# Margay.net
KiCad netlist of a schematic drawn in EAGLE
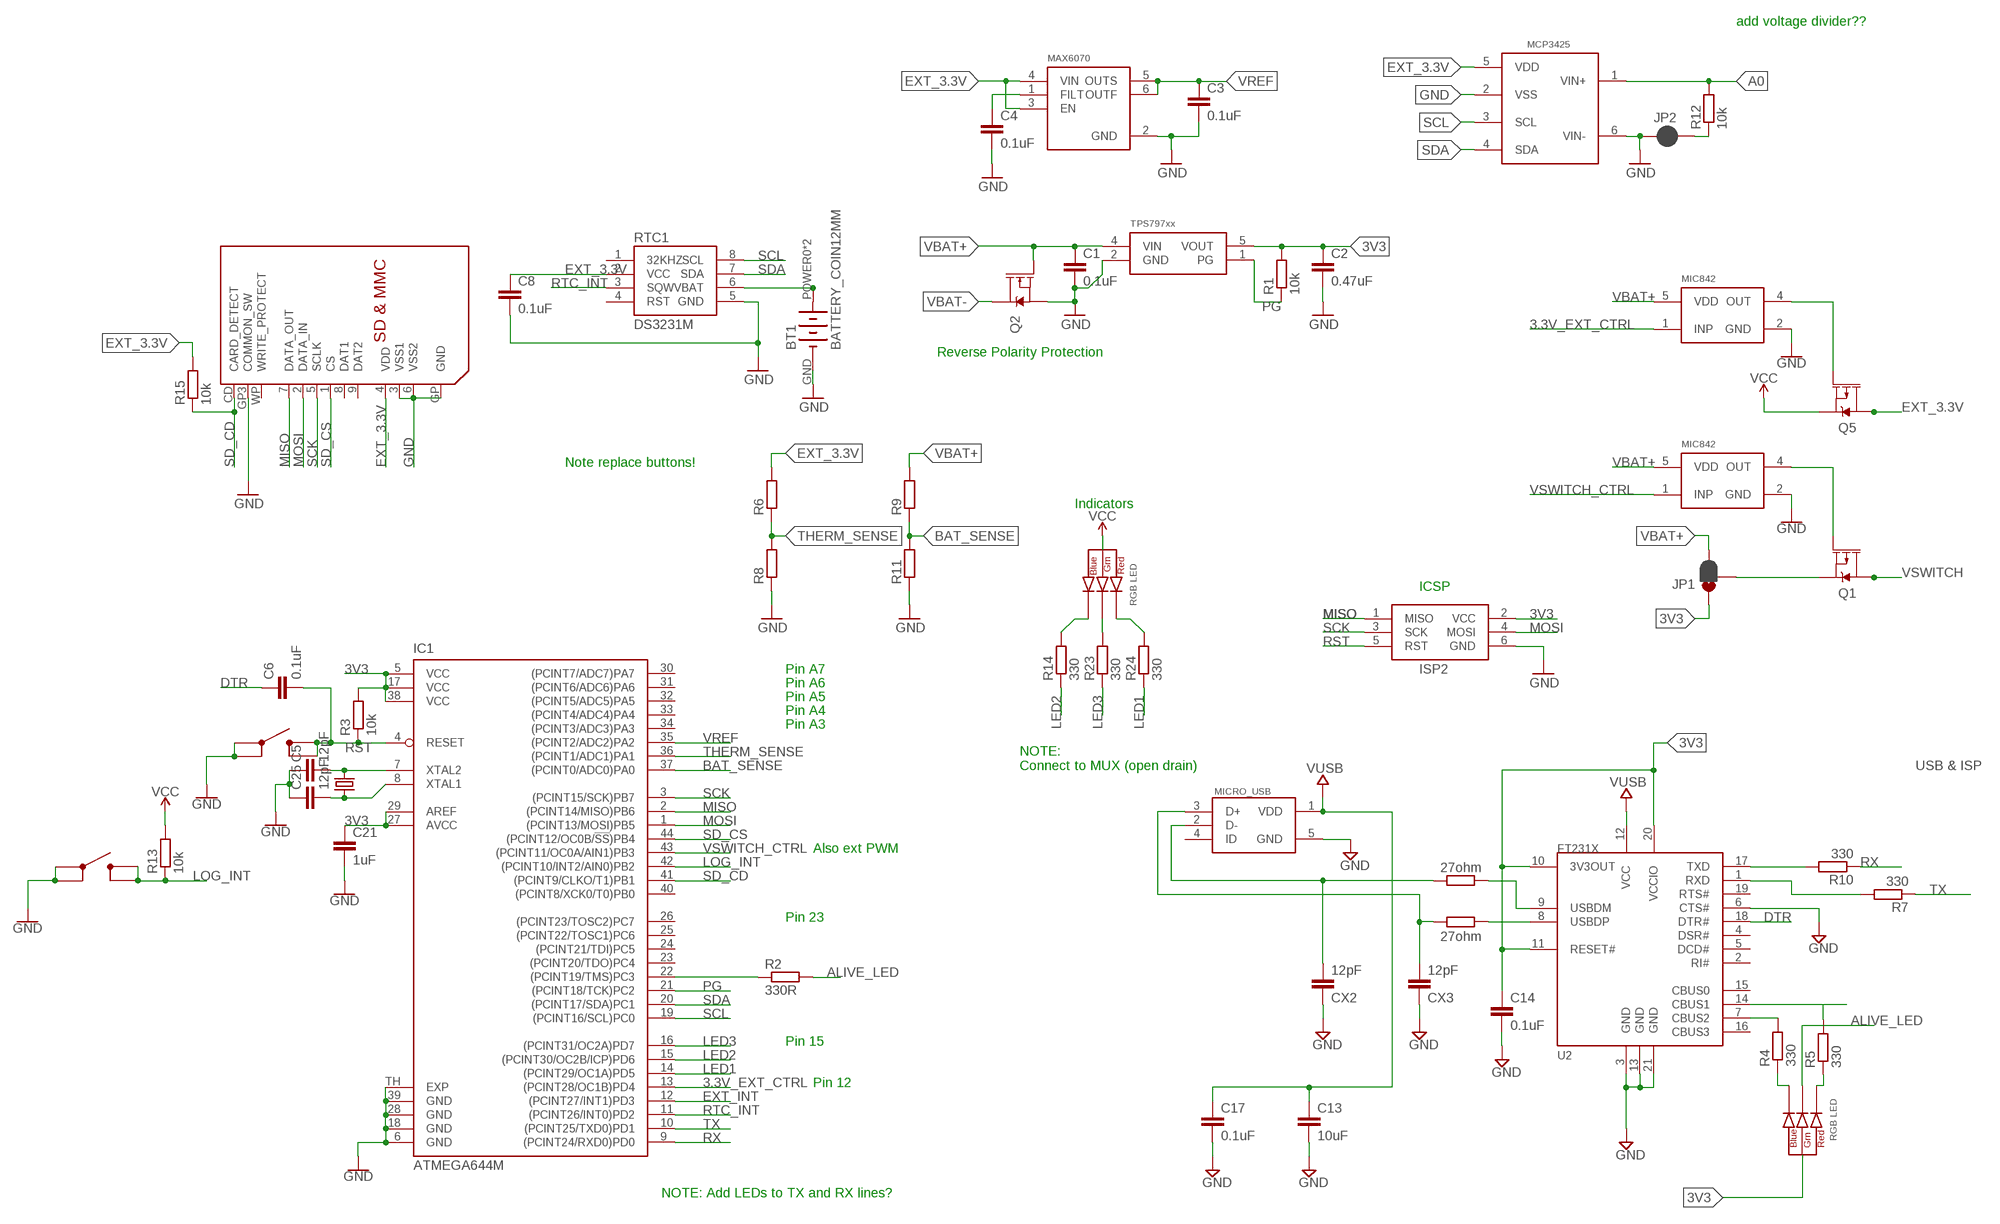
[diagram p0: schematic, sheet 1]
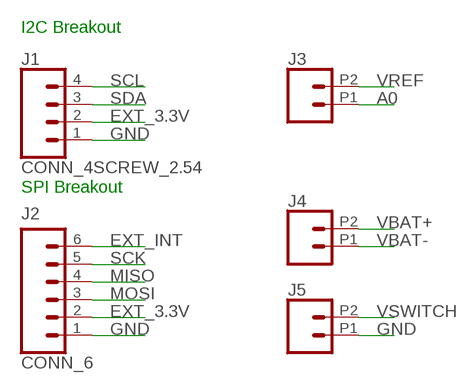
[diagram p1: schematic, sheet 2]

(export (version "E")
  (design (tool "Eeschema 10.0.6"))
  (components
    (comp (ref "J1")
      (value "CONN_4SCREW_2.54")
      (footprint "eagle-import:1X04")
      (libsource (lib "eagle-import") (part "CONN_4SCREW_2.54"))
    )
    (comp (ref "J2")
      (value "CONN_6")
      (footprint "eagle-import:1X06_SCREW")
      (libsource (lib "eagle-import") (part "CONN_6"))
    )
    (comp (ref "J3")
      (value "CONN_022.54MM_SCREWTERM")
      (footprint "eagle-import:1X02_2.54_SCREWTERM")
      (libsource (lib "eagle-import") (part "CONN_022.54MM_SCREWTERM"))
    )
    (comp (ref "J4")
      (value "CONN_022.54MM_SCREWTERM")
      (footprint "eagle-import:1X02_2.54_SCREWTERM")
      (libsource (lib "eagle-import") (part "CONN_022.54MM_SCREWTERM"))
    )
    (comp (ref "J5")
      (value "CONN_022.54MM_SCREWTERM")
      (footprint "eagle-import:1X02_2.54_SCREWTERM")
      (libsource (lib "eagle-import") (part "CONN_022.54MM_SCREWTERM"))
    )
    (comp (ref "BT1")
      (value "BATTERY_COIN12MM")
      (footprint "eagle-import:AWICKERT_LINX_BAT-HLD-012-SMT")
      (fields (field (name "MF") "Linx") (field (name "MPN") "BAT-HLD-012-SMT"))
      (libsource (lib "eagle-import") (part "BATTERY_COIN12MM"))
    )
    (comp (ref "C1")
      (value "0.1uF")
      (footprint "eagle-import:C0603")
      (libsource (lib "eagle-import") (part "bschulz_passives_C-EUC0603"))
    )
    (comp (ref "C2")
      (value "0.47uF")
      (footprint "eagle-import:C0603")
      (libsource (lib "eagle-import") (part "bschulz_passives_C-EUC0603"))
    )
    (comp (ref "C3")
      (value "0.1uF")
      (footprint "eagle-import:C0603")
      (libsource (lib "eagle-import") (part "bschulz_passives_C-EUC0603"))
    )
    (comp (ref "C4")
      (value "0.1uF")
      (footprint "eagle-import:C0603")
      (libsource (lib "eagle-import") (part "bschulz_passives_C-EUC0603"))
    )
    (comp (ref "C5")
      (value "12pF")
      (footprint "eagle-import:C0603")
      (fields
        (field (name "MF") "Samsung")
        (field (name "MPN") "CL10C120JB8NNNC")
        (field (name "DIGIKEY") "1276-1254-1-ND")
        (field (name "MF_1") "Samsung")
        (field (name "MPN_1") "CL10C120JB8NNNC")
      )
      (libsource (lib "eagle-import") (part "C-EUC060312PF"))
    )
    (comp (ref "C6")
      (value "0.1uF")
      (footprint "eagle-import:C0603")
      (fields (field (name "MF") "Samsung") (field (name "MPN") "CL10B104KO8NNNC"))
      (libsource (lib "eagle-import") (part "C-EUC06030.1UF"))
    )
    (comp (ref "C8")
      (value "0.1uF")
      (footprint "eagle-import:C0603")
      (libsource (lib "eagle-import") (part "C-EUC0603"))
    )
    (comp (ref "C13")
      (value "10uF")
      (footprint "eagle-import:C0805")
      (fields (field (name "MF") "Samsung") (field (name "MPN") "CL21A106KQCLRNC"))
      (libsource (lib "eagle-import") (part "C-EUC080510UF"))
    )
    (comp (ref "C14")
      (value "0.1uF")
      (footprint "eagle-import:C0603")
      (fields (field (name "MF") "Samsung") (field (name "MPN") "CL10B104KO8NNNC"))
      (libsource (lib "eagle-import") (part "C-EUC06030.1UF"))
    )
    (comp (ref "C17")
      (value "0.1uF")
      (footprint "eagle-import:C0603")
      (fields (field (name "MF") "Samsung") (field (name "MPN") "CL10B104KO8NNNC"))
      (libsource (lib "eagle-import") (part "C-EUC06030.1UF"))
    )
    (comp (ref "C21")
      (value "1uF")
      (footprint "eagle-import:C0603")
      (fields
        (field (name "MF") "Samsung")
        (field (name "MPN") "1276-6524-1-ND")
        (field (name "DIGIKEY") "1276-6524-1-ND")
        (field (name "MF_1") "Samsung")
        (field (name "MPN_1") "CL10B105MO8NNWC")
      )
      (libsource (lib "eagle-import") (part "C-EUC06031UF"))
    )
    (comp (ref "C25")
      (value "12pF")
      (footprint "eagle-import:C0603")
      (fields
        (field (name "MF") "Samsung")
        (field (name "MPN") "CL10C120JB8NNNC")
        (field (name "DIGIKEY") "1276-1254-1-ND")
        (field (name "MF_1") "Samsung")
        (field (name "MPN_1") "CL10C120JB8NNNC")
      )
      (libsource (lib "eagle-import") (part "C-EUC060312PF"))
    )
    (comp (ref "CX2")
      (value "12pF")
      (footprint "eagle-import:C0603")
      (fields (field (name "MF") "Samsung") (field (name "MPN") "CL10C120JB8NNNC"))
      (libsource (lib "eagle-import") (part "C-EUC060312PF"))
    )
    (comp (ref "CX3")
      (value "12pF")
      (footprint "eagle-import:C0603")
      (fields (field (name "MF") "Samsung") (field (name "MPN") "CL10C120JB8NNNC"))
      (libsource (lib "eagle-import") (part "C-EUC060312PF"))
    )
    (comp (ref "D+")
      (value "27ohm")
      (footprint "eagle-import:R0603")
      (fields
        (field (name "MF") "Yageo")
        (field (name "MPN") "RC0603FR-0727RL")
        (field (name "VALUE_PART") "27")
      )
      (libsource (lib "eagle-import") (part "R-EU_R060327"))
    )
    (comp (ref "D-")
      (value "27ohm")
      (footprint "eagle-import:R0603")
      (fields
        (field (name "MF") "Yageo")
        (field (name "MPN") "RC0603FR-0727RL")
        (field (name "VALUE_PART") "27")
      )
      (libsource (lib "eagle-import") (part "R-EU_R060327"))
    )
    (comp (ref "IC1")
      (value "ATMEGA644M")
      (footprint "eagle-import:MLF44-TH")
      (fields (field (name "MF") "Atmel") (field (name "MPN") "ATMEGA644PA-MUR"))
      (libsource (lib "eagle-import") (part "ATMEGA644M"))
    )
    (comp (ref "ISP2")
      (value "AVRISP-6")
      (footprint "eagle-import:AVRISP")
      (fields (field (name "MF") "Amphenol") (field (name "MPN") "67997-206HLF"))
      (libsource (lib "eagle-import") (part "AVRISP-6"))
    )
    (comp (ref "JP1")
      (value "JUMPER-SMT_3_1-NC_PASTE_SILK")
      (footprint "eagle-import:SMT-JUMPER_3_1-NC_PASTE_SILK")
      (libsource (lib "eagle-import") (part "JUMPER-SMT_3_1-NC_PASTE_SILK"))
    )
    (comp (ref "JP2")
      (value "JUMPER-SMT_2_NC_PASTE_SILK")
      (footprint "eagle-import:SMT-JUMPER_2_NC_PASTE_SILK")
      (libsource (lib "eagle-import") (part "JUMPER-SMT_2_NC_PASTE_SILK"))
    )
    (comp (ref "MICRO_USB")
      (value "MICRO_USB_LONGPADS")
      (footprint "eagle-import:10118194-0001LF_10118194-0001LF_LONGER_PADS")
      (libsource (lib "eagle-import") (part "MICRO_USB_LONGPADS"))
    )
    (comp (ref "Q1")
      (value "MOSFET_PCH-IRLML2244")
      (footprint "eagle-import:SOT23-3")
      (fields (field (name "MF") "Fairchild") (field (name "MPN") "FDN360P"))
      (libsource (lib "eagle-import") (part "MOSFET_PCH-IRLML2244"))
    )
    (comp (ref "Q2")
      (value "MOSFET-NCH-DMG3404L")
      (footprint "eagle-import:SOT23-3")
      (libsource (lib "eagle-import") (part "MOSFET-NCH-DMG3404L"))
    )
    (comp (ref "Q5")
      (value "MOSFET_PCH-IRLML2244")
      (footprint "eagle-import:SOT23-3")
      (fields (field (name "MF") "Fairchild") (field (name "MPN") "FDN360P"))
      (libsource (lib "eagle-import") (part "MOSFET_PCH-IRLML2244"))
    )
    (comp (ref "R1")
      (value "10k")
      (footprint "eagle-import:R0603")
      (libsource (lib "eagle-import") (part "R-EU_R0603"))
    )
    (comp (ref "R2")
      (value "330R")
      (footprint "eagle-import:R0603")
      (libsource (lib "eagle-import") (part "R-EU_R0603"))
    )
    (comp (ref "R3")
      (value "10k")
      (footprint "eagle-import:R0603")
      (fields
        (field (name "MF") "Yageo")
        (field (name "MPN") "RC0603FR-0710KL")
        (field (name "DIGIKEY") "311-10.0KHRCT-ND")
      )
      (libsource (lib "eagle-import") (part "R-EU_R060310K"))
    )
    (comp (ref "R4")
      (value "330")
      (footprint "eagle-import:R0603")
      (fields
        (field (name "MF") "Yageo")
        (field (name "MPN") "RC0603FR-07330RL")
        (field (name "MPN_1") "RC0603FR-07330RL")
      )
      (libsource (lib "eagle-import") (part "R-EU_R0603330"))
    )
    (comp (ref "R5")
      (value "330")
      (footprint "eagle-import:R0603")
      (fields
        (field (name "MF") "Yageo")
        (field (name "MPN") "RC0603FR-07330RL")
        (field (name "DIGIKEY") "311-330HRCT-ND")
        (field (name "MF_1") "Yageo")
        (field (name "MPN_1") "RC0603FR-07330RL")
      )
      (libsource (lib "eagle-import") (part "R-EU_R0603330"))
    )
    (comp (ref "R6")
      (value "R-EU_R0603")
      (footprint "eagle-import:R0603")
      (libsource (lib "eagle-import") (part "R-EU_R0603"))
    )
    (comp (ref "R7")
      (value "330")
      (footprint "eagle-import:R0603")
      (fields
        (field (name "MF") "Yageo")
        (field (name "MPN") "RC0603FR-07330RL")
        (field (name "MPN_1") "RC0603FR-07330RL")
      )
      (libsource (lib "eagle-import") (part "R-EU_R0603330"))
    )
    (comp (ref "R8")
      (value "R-EU_R0603")
      (footprint "eagle-import:R0603")
      (libsource (lib "eagle-import") (part "R-EU_R0603"))
    )
    (comp (ref "R9")
      (value "R-EU_R0603")
      (footprint "eagle-import:R0603")
      (libsource (lib "eagle-import") (part "R-EU_R0603"))
    )
    (comp (ref "R10")
      (value "330")
      (footprint "eagle-import:R0603")
      (fields
        (field (name "MF") "Yageo")
        (field (name "MPN") "RC0603FR-07330RL")
        (field (name "MPN_1") "RC0603FR-07330RL")
      )
      (libsource (lib "eagle-import") (part "R-EU_R0603330"))
    )
    (comp (ref "R11")
      (value "R-EU_R0603")
      (footprint "eagle-import:R0603")
      (libsource (lib "eagle-import") (part "R-EU_R0603"))
    )
    (comp (ref "R12")
      (value "10k")
      (footprint "eagle-import:R0603")
      (libsource (lib "eagle-import") (part "R-EU_R0603"))
    )
    (comp (ref "R13")
      (value "10k")
      (footprint "eagle-import:R0603")
      (fields
        (field (name "MF") "Yageo")
        (field (name "MPN") "RC0603FR-0710KL")
        (field (name "DIGIKEY") "311-10.0KHRCT-ND")
      )
      (libsource (lib "eagle-import") (part "R-EU_R060310K"))
    )
    (comp (ref "R14")
      (value "330")
      (footprint "eagle-import:R0603")
      (fields
        (field (name "MF") "Yageo")
        (field (name "MPN") "RC0603FR-07330RL")
        (field (name "MPN_1") "RC0603FR-07330RL")
      )
      (libsource (lib "eagle-import") (part "R-EU_R0603330"))
    )
    (comp (ref "R15")
      (value "10k")
      (footprint "eagle-import:R0603")
      (libsource (lib "eagle-import") (part "R-EU_R0603"))
    )
    (comp (ref "R23")
      (value "330")
      (footprint "eagle-import:R0603")
      (fields
        (field (name "MF") "Yageo")
        (field (name "MPN") "RC0603FR-07330RL")
        (field (name "MPN_1") "RC0603FR-07330RL")
      )
      (libsource (lib "eagle-import") (part "R-EU_R0603330"))
    )
    (comp (ref "R24")
      (value "330")
      (footprint "eagle-import:R0603")
      (fields
        (field (name "MF") "Yageo")
        (field (name "MPN") "RC0603FR-07330RL")
        (field (name "MPN_1") "RC0603FR-07330RL")
      )
      (libsource (lib "eagle-import") (part "R-EU_R0603330"))
    )
    (comp (ref "RTC1")
      (value "DS3231M")
      (footprint "eagle-import:SO08")
      (fields (field (name "MF") "Maxim") (field (name "MPN") "DS3231MZ+"))
      (libsource (lib "eagle-import") (part "DS3231M"))
    )
    (comp (ref "U$1")
      (value "CRYSTAL_5X3.2_2LEAD")
      (footprint "eagle-import:CRYSTAL_5X3.2_2-SMD")
      (libsource (lib "eagle-import") (part "CRYSTAL_5X3.2_2LEAD"))
    )
    (comp (ref "U$3")
      (value "SDMMC06132")
      (footprint "eagle-import:06132")
      (libsource (lib "eagle-import") (part "SDMMC06132"))
    )
    (comp (ref "U$4")
      (value "MIC842")
      (footprint "eagle-import:DCK_R-PDSO-G5")
      (libsource (lib "eagle-import") (part "MIC842"))
    )
    (comp (ref "U$5")
      (value "BUTTON4.2X3.2")
      (footprint "eagle-import:SWITCH_4.2X3.2")
      (libsource (lib "eagle-import") (part "BUTTON4.2X3.2"))
    )
    (comp (ref "U$6")
      (value "TPS79733")
      (footprint "eagle-import:DCK_R-PDSO-G5")
      (fields (field (name "MF") "TI") (field (name "MPN") "TPS79733DCKR"))
      (libsource (lib "eagle-import") (part "TPS79733"))
    )
    (comp (ref "U$7")
      (value "MAX6070AAUT18")
      (footprint "eagle-import:SOT23-6L")
      (fields (field (name "MF") "Maxim") (field (name "MPN") "MAX6070BAUT18+T"))
      (libsource (lib "eagle-import") (part "MAX6070AAUT18"))
    )
    (comp (ref "U$8")
      (value "MCP3425")
      (footprint "eagle-import:SOT23-6L")
      (fields (field (name "MF") "Microchip") (field (name "MPN") "MCP3425A0T-E/CH"))
      (libsource (lib "eagle-import") (part "MCP3425"))
    )
    (comp (ref "U$9")
      (value "BUTTON4.2X3.2")
      (footprint "eagle-import:SWITCH_4.2X3.2")
      (libsource (lib "eagle-import") (part "BUTTON4.2X3.2"))
    )
    (comp (ref "U$15")
      (value "CLVBA-FKA")
      (footprint "eagle-import:CLVBA-FKA")
      (fields (field (name "MF") "Cree") (field (name "MPN") "CLVBA-FKA-CAEDH8BBB7A363"))
      (libsource (lib "eagle-import") (part "CLVBA-FKA"))
    )
    (comp (ref "U$16")
      (value "CLVBA-FKA")
      (footprint "eagle-import:CLVBA-FKA")
      (fields (field (name "MF") "Cree") (field (name "MPN") "CLVBA-FKA-CAEDH8BBB7A363"))
      (libsource (lib "eagle-import") (part "CLVBA-FKA"))
    )
    (comp (ref "U$18")
      (value "MIC842")
      (footprint "eagle-import:DCK_R-PDSO-G5")
      (libsource (lib "eagle-import") (part "MIC842"))
    )
    (comp (ref "U2")
      (value "FT231X-Q")
      (footprint "eagle-import:QFN20")
      (fields (field (name "MF") "FTDI") (field (name "MPN") "FT231XQ-R"))
      (libsource (lib "eagle-import") (part "FT231X-Q"))
    )
  )
  (nets
    (net (code "1") (name "3.3V_EXT_CTRL") (class "Default")
      (node (ref "IC1") (pin "13") (pinfunction "(PCINT28/OC1B)PD4_13") (pintype "bidirectional"))
      (node (ref "U$18") (pin "1") (pinfunction "INP_1") (pintype "input"))
    )
    (net (code "2") (name "3V3") (class "Default")
      (node (ref "C14") (pin "1") (pinfunction "1_1") (pintype "passive"))
      (node (ref "C2") (pin "1") (pinfunction "1_1") (pintype "passive"))
      (node (ref "C21") (pin "1") (pinfunction "1_1") (pintype "passive"))
      (node (ref "IC1") (pin "17") (pinfunction "VCC_17") (pintype "power_in"))
      (node (ref "IC1") (pin "27") (pinfunction "AVCC_27") (pintype "power_in"))
      (node (ref "IC1") (pin "29") (pinfunction "AREF_29") (pintype "passive"))
      (node (ref "IC1") (pin "38") (pinfunction "VCC_38") (pintype "power_in"))
      (node (ref "IC1") (pin "5") (pinfunction "VCC_5") (pintype "power_in"))
      (node (ref "ISP2") (pin "2") (pinfunction "VCC_2") (pintype "power_in"))
      (node (ref "JP1") (pin "1") (pinfunction "1_1") (pintype "passive"))
      (node (ref "Q5") (pin "2") (pinfunction "S_2") (pintype "bidirectional"))
      (node (ref "R1") (pin "2") (pinfunction "2_2") (pintype "passive"))
      (node (ref "R13") (pin "2") (pinfunction "2_2") (pintype "passive"))
      (node (ref "R3") (pin "2") (pinfunction "2_2") (pintype "passive"))
      (node (ref "U$15") (pin "2") (pinfunction "ANODE_2") (pintype "bidirectional"))
      (node (ref "U$16") (pin "2") (pinfunction "ANODE_2") (pintype "bidirectional"))
      (node (ref "U$6") (pin "5") (pinfunction "VOUT_5") (pintype "bidirectional"))
      (node (ref "U2") (pin "10") (pinfunction "3V3OUT_10") (pintype "bidirectional"))
      (node (ref "U2") (pin "11") (pinfunction "RESET#_11") (pintype "bidirectional"))
      (node (ref "U2") (pin "20") (pinfunction "VCCIO_20") (pintype "bidirectional"))
    )
    (net (code "3") (name "A0") (class "Default")
      (node (ref "J3") (pin "P1") (pinfunction "1_P1") (pintype "passive"))
      (node (ref "R12") (pin "2") (pinfunction "2_2") (pintype "passive"))
      (node (ref "U$8") (pin "1") (pinfunction "VIN+_1") (pintype "input"))
    )
    (net (code "4") (name "ALIVE_LED") (class "Default")
      (node (ref "R2") (pin "2") (pinfunction "2_2") (pintype "passive"))
      (node (ref "U$16") (pin "4") (pinfunction "GREEN_CATH_4") (pintype "bidirectional"))
    )
    (net (code "5") (name "BAT_SENSE") (class "Default")
      (node (ref "IC1") (pin "37") (pinfunction "(PCINT0/ADC0)PA0_37") (pintype "bidirectional"))
      (node (ref "R11") (pin "2") (pinfunction "2_2") (pintype "passive"))
      (node (ref "R9") (pin "1") (pinfunction "1_1") (pintype "passive"))
    )
    (net (code "6") (name "DTR") (class "Default")
      (node (ref "C6") (pin "1") (pinfunction "1_1") (pintype "passive"))
      (node (ref "U2") (pin "18") (pinfunction "DTR#_18") (pintype "bidirectional"))
    )
    (net (code "7") (name "EXT_3.3V") (class "Default")
      (node (ref "C8") (pin "1") (pinfunction "1_1") (pintype "passive"))
      (node (ref "J1") (pin "2") (pinfunction "2_2") (pintype "passive"))
      (node (ref "J2") (pin "2") (pinfunction "2_2") (pintype "passive"))
      (node (ref "Q5") (pin "3") (pinfunction "D_3") (pintype "bidirectional"))
      (node (ref "R15") (pin "2") (pinfunction "2_2") (pintype "passive"))
      (node (ref "R6") (pin "2") (pinfunction "2_2") (pintype "passive"))
      (node (ref "RTC1") (pin "2") (pinfunction "VCC_2") (pintype "power_in"))
      (node (ref "U$3") (pin "4") (pinfunction "VDD_4") (pintype "power_in"))
      (node (ref "U$7") (pin "3") (pinfunction "EN_3") (pintype "bidirectional"))
      (node (ref "U$7") (pin "4") (pinfunction "VIN_4") (pintype "bidirectional"))
      (node (ref "U$8") (pin "5") (pinfunction "VDD_5") (pintype "passive"))
    )
    (net (code "8") (name "EXT_INT") (class "Default")
      (node (ref "IC1") (pin "12") (pinfunction "(PCINT27/INT1)PD3_12") (pintype "bidirectional"))
      (node (ref "J2") (pin "6") (pinfunction "6_6") (pintype "passive"))
    )
    (net (code "9") (name "GND") (class "Default")
      (node (ref "BT1") (pin "GND") (pinfunction "-_GND") (pintype "passive"))
      (node (ref "C1") (pin "2") (pinfunction "2_2") (pintype "passive"))
      (node (ref "C13") (pin "2") (pinfunction "2_2") (pintype "passive"))
      (node (ref "C14") (pin "2") (pinfunction "2_2") (pintype "passive"))
      (node (ref "C17") (pin "2") (pinfunction "2_2") (pintype "passive"))
      (node (ref "C2") (pin "2") (pinfunction "2_2") (pintype "passive"))
      (node (ref "C21") (pin "2") (pinfunction "2_2") (pintype "passive"))
      (node (ref "C25") (pin "1") (pinfunction "1_1") (pintype "passive"))
      (node (ref "C3") (pin "2") (pinfunction "2_2") (pintype "passive"))
      (node (ref "C4") (pin "2") (pinfunction "2_2") (pintype "passive"))
      (node (ref "C5") (pin "1") (pinfunction "1_1") (pintype "passive"))
      (node (ref "C8") (pin "2") (pinfunction "2_2") (pintype "passive"))
      (node (ref "CX2") (pin "1") (pinfunction "1_1") (pintype "passive"))
      (node (ref "CX3") (pin "1") (pinfunction "1_1") (pintype "passive"))
      (node (ref "IC1") (pin "18") (pinfunction "GND_18") (pintype "power_in"))
      (node (ref "IC1") (pin "28") (pinfunction "GND_28") (pintype "power_in"))
      (node (ref "IC1") (pin "39") (pinfunction "GND_39") (pintype "power_in"))
      (node (ref "IC1") (pin "6") (pinfunction "GND_6") (pintype "power_in"))
      (node (ref "IC1") (pin "TH") (pinfunction "EXP_TH") (pintype "power_in"))
      (node (ref "ISP2") (pin "6") (pinfunction "GND_6") (pintype "power_in"))
      (node (ref "J1") (pin "1") (pinfunction "1_1") (pintype "passive"))
      (node (ref "J2") (pin "1") (pinfunction "1_1") (pintype "passive"))
      (node (ref "J5") (pin "P1") (pinfunction "1_P1") (pintype "passive"))
      (node (ref "JP2") (pin "1") (pinfunction "1_1") (pintype "passive"))
      (node (ref "MICRO_USB") (pin "5") (pinfunction "GND_5") (pintype "power_in"))
      (node (ref "Q2") (pin "2") (pinfunction "S_2") (pintype "bidirectional"))
      (node (ref "R11") (pin "1") (pinfunction "1_1") (pintype "passive"))
      (node (ref "R8") (pin "1") (pinfunction "1_1") (pintype "passive"))
      (node (ref "RTC1") (pin "5") (pinfunction "GND_5") (pintype "power_in"))
      (node (ref "U$18") (pin "2") (pinfunction "GND_2") (pintype "power_in"))
      (node (ref "U$3") (pin "3") (pinfunction "VSS1_3") (pintype "power_in"))
      (node (ref "U$3") (pin "6") (pinfunction "VSS2_6") (pintype "power_in"))
      (node (ref "U$3") (pin "GP") (pinfunction "GND_GP") (pintype "power_in"))
      (node (ref "U$3") (pin "GP3") (pinfunction "COMMON_SW_GP3") (pintype "passive"))
      (node (ref "U$4") (pin "2") (pinfunction "GND_2") (pintype "power_in"))
      (node (ref "U$5") (pin "1") (pinfunction "1_1") (pintype "bidirectional"))
      (node (ref "U$5") (pin "2") (pinfunction "2_2") (pintype "bidirectional"))
      (node (ref "U$6") (pin "2") (pinfunction "GND_2") (pintype "bidirectional"))
      (node (ref "U$7") (pin "2") (pinfunction "GND_2") (pintype "bidirectional"))
      (node (ref "U$8") (pin "2") (pinfunction "VSS_2") (pintype "passive"))
      (node (ref "U$8") (pin "6") (pinfunction "VIN-_6") (pintype "input"))
      (node (ref "U$9") (pin "1") (pinfunction "1_1") (pintype "bidirectional"))
      (node (ref "U$9") (pin "2") (pinfunction "2_2") (pintype "bidirectional"))
      (node (ref "U2") (pin "13") (pinfunction "GND_13") (pintype "bidirectional"))
      (node (ref "U2") (pin "21") (pinfunction "GND_21") (pintype "bidirectional"))
      (node (ref "U2") (pin "3") (pinfunction "GND_3") (pintype "bidirectional"))
      (node (ref "U2") (pin "6") (pinfunction "CTS#_6") (pintype "bidirectional"))
    )
    (net (code "10") (name "LED1") (class "Default")
      (node (ref "IC1") (pin "14") (pinfunction "(PCINT29/OC1A)PD5_14") (pintype "bidirectional"))
      (node (ref "R24") (pin "1") (pinfunction "1_1") (pintype "passive"))
    )
    (net (code "11") (name "LED2") (class "Default")
      (node (ref "IC1") (pin "15") (pinfunction "(PCINT30/OC2B/ICP)PD6_15") (pintype "bidirectional"))
      (node (ref "R14") (pin "1") (pinfunction "1_1") (pintype "passive"))
    )
    (net (code "12") (name "LED3") (class "Default")
      (node (ref "IC1") (pin "16") (pinfunction "(PCINT31/OC2A)PD7_16") (pintype "bidirectional"))
      (node (ref "R23") (pin "1") (pinfunction "1_1") (pintype "passive"))
    )
    (net (code "13") (name "LOG_INT") (class "Default")
      (node (ref "IC1") (pin "42") (pinfunction "(PCINT10/INT2/AIN0)PB2_42") (pintype "bidirectional"))
      (node (ref "R13") (pin "1") (pinfunction "1_1") (pintype "passive"))
      (node (ref "U$5") (pin "3") (pinfunction "4_3") (pintype "bidirectional"))
      (node (ref "U$5") (pin "4") (pinfunction "3_4") (pintype "bidirectional"))
    )
    (net (code "14") (name "MISO") (class "Default")
      (node (ref "IC1") (pin "2") (pinfunction "(PCINT14/MISO)PB6_2") (pintype "bidirectional"))
      (node (ref "ISP2") (pin "1") (pinfunction "MISO_1") (pintype "input"))
      (node (ref "J2") (pin "4") (pinfunction "4_4") (pintype "passive"))
      (node (ref "U$3") (pin "7") (pinfunction "DATA_OUT_7") (pintype "output"))
    )
    (net (code "15") (name "MOSI") (class "Default")
      (node (ref "IC1") (pin "1") (pinfunction "(PCINT13/MOSI)PB5_1") (pintype "bidirectional"))
      (node (ref "ISP2") (pin "4") (pinfunction "MOSI_4") (pintype "output"))
      (node (ref "J2") (pin "3") (pinfunction "3_3") (pintype "passive"))
      (node (ref "U$3") (pin "2") (pinfunction "DATA_IN_2") (pintype "input"))
    )
    (net (code "16") (name "Net-(IC1-(PCINT19{slash}TMS)PC3)") (class "Default")
      (node (ref "IC1") (pin "22") (pinfunction "(PCINT19/TMS)PC3_22") (pintype "output"))
      (node (ref "R2") (pin "1") (pinfunction "1_1") (pintype "passive"))
    )
    (net (code "17") (name "Net-(IC1-XTAL1)") (class "Default")
      (node (ref "C25") (pin "2") (pinfunction "2_2") (pintype "passive"))
      (node (ref "IC1") (pin "8") (pinfunction "XTAL1_8") (pintype "bidirectional"))
      (node (ref "U$1") (pin "OSC1") (pinfunction "1_OSC1") (pintype "passive"))
    )
    (net (code "18") (name "Net-(IC1-XTAL2)") (class "Default")
      (node (ref "C5") (pin "2") (pinfunction "2_2") (pintype "passive"))
      (node (ref "IC1") (pin "7") (pinfunction "XTAL2_7") (pintype "bidirectional"))
      (node (ref "U$1") (pin "OSC2") (pinfunction "2_OSC2") (pintype "passive"))
    )
    (net (code "19") (name "Net-(JP2-Pad2)") (class "Default")
      (node (ref "JP2") (pin "2") (pinfunction "2_2") (pintype "passive"))
      (node (ref "R12") (pin "1") (pinfunction "1_1") (pintype "passive"))
    )
    (net (code "20") (name "Net-(MICRO_USB-D+)") (class "Default")
      (node (ref "CX3") (pin "2") (pinfunction "2_2") (pintype "passive"))
      (node (ref "D+") (pin "2") (pinfunction "2_2") (pintype "passive"))
      (node (ref "MICRO_USB") (pin "3") (pinfunction "D+_3") (pintype "bidirectional"))
    )
    (net (code "21") (name "Net-(MICRO_USB-D-)") (class "Default")
      (node (ref "CX2") (pin "2") (pinfunction "2_2") (pintype "passive"))
      (node (ref "D-") (pin "2") (pinfunction "2_2") (pintype "passive"))
      (node (ref "MICRO_USB") (pin "2") (pinfunction "D-_2") (pintype "bidirectional"))
    )
    (net (code "22") (name "Net-(Q1-G)") (class "Default")
      (node (ref "Q1") (pin "1") (pinfunction "G_1") (pintype "bidirectional"))
      (node (ref "U$4") (pin "4") (pinfunction "OUT_4") (pintype "output"))
    )
    (net (code "23") (name "Net-(Q1-S)") (class "Default")
      (node (ref "JP1") (pin "2") (pinfunction "2_2") (pintype "passive"))
      (node (ref "Q1") (pin "2") (pinfunction "S_2") (pintype "bidirectional"))
    )
    (net (code "24") (name "Net-(Q5-G)") (class "Default")
      (node (ref "Q5") (pin "1") (pinfunction "G_1") (pintype "bidirectional"))
      (node (ref "U$18") (pin "4") (pinfunction "OUT_4") (pintype "output"))
    )
    (net (code "25") (name "Net-(RTC1-VBAT)") (class "Default")
      (node (ref "BT1") (pin "POWER0") (pinfunction "+_POWER0") (pintype "passive"))
      (node (ref "BT1") (pin "POWER1") (pinfunction "+_POWER1") (pintype "passive"))
      (node (ref "RTC1") (pin "6") (pinfunction "VBAT_6") (pintype "power_in"))
    )
    (net (code "26") (name "Net-(U$7-FILT)") (class "Default")
      (node (ref "C4") (pin "1") (pinfunction "1_1") (pintype "passive"))
      (node (ref "U$7") (pin "1") (pinfunction "FILT_1") (pintype "bidirectional"))
    )
    (net (code "27") (name "Net-(U$15-BLUE_CATH)") (class "Default")
      (node (ref "R14") (pin "2") (pinfunction "2_2") (pintype "passive"))
      (node (ref "U$15") (pin "3") (pinfunction "BLUE_CATH_3") (pintype "bidirectional"))
    )
    (net (code "28") (name "Net-(U$15-GREEN_CATH)") (class "Default")
      (node (ref "R23") (pin "2") (pinfunction "2_2") (pintype "passive"))
      (node (ref "U$15") (pin "4") (pinfunction "GREEN_CATH_4") (pintype "bidirectional"))
    )
    (net (code "29") (name "Net-(U$15-RED_CATH)") (class "Default")
      (node (ref "R24") (pin "2") (pinfunction "2_2") (pintype "passive"))
      (node (ref "U$15") (pin "1") (pinfunction "RED_CATH_1") (pintype "bidirectional"))
    )
    (net (code "30") (name "Net-(U$16-BLUE_CATH)") (class "Default")
      (node (ref "R4") (pin "1") (pinfunction "1_1") (pintype "passive"))
      (node (ref "U$16") (pin "3") (pinfunction "BLUE_CATH_3") (pintype "bidirectional"))
    )
    (net (code "31") (name "Net-(U$16-RED_CATH)") (class "Default")
      (node (ref "R5") (pin "1") (pinfunction "1_1") (pintype "passive"))
      (node (ref "U$16") (pin "1") (pinfunction "RED_CATH_1") (pintype "bidirectional"))
    )
    (net (code "32") (name "Net-(U2-CBUS1)") (class "Default")
      (node (ref "R5") (pin "2") (pinfunction "2_2") (pintype "passive"))
      (node (ref "U2") (pin "14") (pinfunction "CBUS1_14") (pintype "bidirectional"))
    )
    (net (code "33") (name "Net-(U2-CBUS2)") (class "Default")
      (node (ref "R4") (pin "2") (pinfunction "2_2") (pintype "passive"))
      (node (ref "U2") (pin "7") (pinfunction "CBUS2_7") (pintype "bidirectional"))
    )
    (net (code "34") (name "Net-(U2-RXD)") (class "Default")
      (node (ref "R7") (pin "2") (pinfunction "2_2") (pintype "passive"))
      (node (ref "U2") (pin "1") (pinfunction "RXD_1") (pintype "bidirectional"))
    )
    (net (code "35") (name "Net-(U2-TXD)") (class "Default")
      (node (ref "R10") (pin "2") (pinfunction "2_2") (pintype "passive"))
      (node (ref "U2") (pin "17") (pinfunction "TXD_17") (pintype "bidirectional"))
    )
    (net (code "36") (name "Net-(U2-USBDM)") (class "Default")
      (node (ref "D-") (pin "1") (pinfunction "1_1") (pintype "passive"))
      (node (ref "U2") (pin "9") (pinfunction "USBDM_9") (pintype "bidirectional"))
    )
    (net (code "37") (name "Net-(U2-USBDP)") (class "Default")
      (node (ref "D+") (pin "1") (pinfunction "1_1") (pintype "passive"))
      (node (ref "U2") (pin "8") (pinfunction "USBDP_8") (pintype "bidirectional"))
    )
    (net (code "38") (name "PG") (class "Default")
      (node (ref "IC1") (pin "21") (pinfunction "(PCINT18/TCK)PC2_21") (pintype "output"))
      (node (ref "R1") (pin "1") (pinfunction "1_1") (pintype "passive"))
      (node (ref "U$6") (pin "1") (pinfunction "PG_1") (pintype "bidirectional"))
    )
    (net (code "39") (name "RST") (class "Default")
      (node (ref "C6") (pin "2") (pinfunction "2_2") (pintype "passive"))
      (node (ref "IC1") (pin "4") (pinfunction "RESET_4") (pintype "input"))
      (node (ref "ISP2") (pin "5") (pinfunction "RST_5") (pintype "output"))
      (node (ref "R3") (pin "1") (pinfunction "1_1") (pintype "passive"))
      (node (ref "U$9") (pin "3") (pinfunction "4_3") (pintype "bidirectional"))
      (node (ref "U$9") (pin "4") (pinfunction "3_4") (pintype "bidirectional"))
    )
    (net (code "40") (name "RTC_INT") (class "Default")
      (node (ref "IC1") (pin "11") (pinfunction "(PCINT26/INT0)PD2_11") (pintype "bidirectional"))
      (node (ref "RTC1") (pin "3") (pinfunction "SQW_3") (pintype "output"))
    )
    (net (code "41") (name "RX") (class "Default")
      (node (ref "IC1") (pin "9") (pinfunction "(PCINT24/RXD0)PD0_9") (pintype "bidirectional"))
      (node (ref "R10") (pin "1") (pinfunction "1_1") (pintype "passive"))
    )
    (net (code "42") (name "SCK") (class "Default")
      (node (ref "IC1") (pin "3") (pinfunction "(PCINT15/SCK)PB7_3") (pintype "bidirectional"))
      (node (ref "ISP2") (pin "3") (pinfunction "SCK_3") (pintype "output"))
      (node (ref "J2") (pin "5") (pinfunction "5_5") (pintype "passive"))
      (node (ref "U$3") (pin "5") (pinfunction "SCLK_5") (pintype "input"))
    )
    (net (code "43") (name "SCL") (class "Default")
      (node (ref "IC1") (pin "19") (pinfunction "(PCINT16/SCL)PC0_19") (pintype "output"))
      (node (ref "J1") (pin "4") (pinfunction "4_4") (pintype "passive"))
      (node (ref "RTC1") (pin "8") (pinfunction "SCL_8") (pintype "bidirectional"))
      (node (ref "U$8") (pin "3") (pinfunction "SCL_3") (pintype "bidirectional"))
    )
    (net (code "44") (name "SDA") (class "Default")
      (node (ref "IC1") (pin "20") (pinfunction "(PCINT17/SDA)PC1_20") (pintype "output"))
      (node (ref "J1") (pin "3") (pinfunction "3_3") (pintype "passive"))
      (node (ref "RTC1") (pin "7") (pinfunction "SDA_7") (pintype "bidirectional"))
      (node (ref "U$8") (pin "4") (pinfunction "SDA_4") (pintype "bidirectional"))
    )
    (net (code "45") (name "SD_CD") (class "Default")
      (node (ref "IC1") (pin "41") (pinfunction "(PCINT9/CLKO/T1)PB1_41") (pintype "bidirectional"))
      (node (ref "R15") (pin "1") (pinfunction "1_1") (pintype "passive"))
      (node (ref "U$3") (pin "CD") (pinfunction "CARD_DETECT_CD") (pintype "passive"))
    )
    (net (code "46") (name "SD_CS") (class "Default")
      (node (ref "IC1") (pin "44") (pinfunction "(PCINT12/OC0B/~{SS})PB4_44") (pintype "bidirectional"))
      (node (ref "U$3") (pin "1") (pinfunction "CS_1") (pintype "input"))
    )
    (net (code "47") (name "THERM_SENSE") (class "Default")
      (node (ref "IC1") (pin "36") (pinfunction "(PCINT1/ADC1)PA1_36") (pintype "bidirectional"))
      (node (ref "R6") (pin "1") (pinfunction "1_1") (pintype "passive"))
      (node (ref "R8") (pin "2") (pinfunction "2_2") (pintype "passive"))
    )
    (net (code "48") (name "TX") (class "Default")
      (node (ref "IC1") (pin "10") (pinfunction "(PCINT25/TXD0)PD1_10") (pintype "bidirectional"))
      (node (ref "R7") (pin "1") (pinfunction "1_1") (pintype "passive"))
    )
    (net (code "49") (name "VBAT+") (class "Default")
      (node (ref "C1") (pin "1") (pinfunction "1_1") (pintype "passive"))
      (node (ref "J4") (pin "P2") (pinfunction "2_P2") (pintype "passive"))
      (node (ref "JP1") (pin "3") (pinfunction "3_3") (pintype "passive"))
      (node (ref "Q2") (pin "1") (pinfunction "G_1") (pintype "bidirectional"))
      (node (ref "R9") (pin "2") (pinfunction "2_2") (pintype "passive"))
      (node (ref "U$18") (pin "5") (pinfunction "VDD_5") (pintype "power_in"))
      (node (ref "U$4") (pin "5") (pinfunction "VDD_5") (pintype "power_in"))
      (node (ref "U$6") (pin "4") (pinfunction "VIN_4") (pintype "bidirectional"))
    )
    (net (code "50") (name "VBAT-") (class "Default")
      (node (ref "J4") (pin "P1") (pinfunction "1_P1") (pintype "passive"))
      (node (ref "Q2") (pin "3") (pinfunction "D_3") (pintype "bidirectional"))
    )
    (net (code "51") (name "VREF") (class "Default")
      (node (ref "C3") (pin "1") (pinfunction "1_1") (pintype "passive"))
      (node (ref "IC1") (pin "35") (pinfunction "(PCINT2/ADC2)PA2_35") (pintype "bidirectional"))
      (node (ref "J3") (pin "P2") (pinfunction "2_P2") (pintype "passive"))
      (node (ref "U$7") (pin "5") (pinfunction "OUTS_5") (pintype "bidirectional"))
      (node (ref "U$7") (pin "6") (pinfunction "OUTF_6") (pintype "bidirectional"))
    )
    (net (code "52") (name "VSWITCH") (class "Default")
      (node (ref "J5") (pin "P2") (pinfunction "2_P2") (pintype "passive"))
      (node (ref "Q1") (pin "3") (pinfunction "D_3") (pintype "bidirectional"))
    )
    (net (code "53") (name "VSWITCH_CTRL") (class "Default")
      (node (ref "IC1") (pin "43") (pinfunction "(PCINT11/OC0A/AIN1)PB3_43") (pintype "bidirectional"))
      (node (ref "U$4") (pin "1") (pinfunction "INP_1") (pintype "input"))
    )
    (net (code "54") (name "VUSB") (class "Default")
      (node (ref "C13") (pin "1") (pinfunction "1_1") (pintype "passive"))
      (node (ref "C17") (pin "1") (pinfunction "1_1") (pintype "passive"))
      (node (ref "MICRO_USB") (pin "1") (pinfunction "VDD_1") (pintype "power_in"))
      (node (ref "U2") (pin "12") (pinfunction "VCC_12") (pintype "bidirectional"))
    )
    (net (code "55") (name "unconnected-(IC1-(PCINT3{slash}ADC3)PA3-Pad34)") (class "Default")
      (node (ref "IC1") (pin "34") (pinfunction "(PCINT3/ADC3)PA3_34") (pintype "bidirectional"))
    )
    (net (code "56") (name "unconnected-(IC1-(PCINT4{slash}ADC4)PA4-Pad33)") (class "Default")
      (node (ref "IC1") (pin "33") (pinfunction "(PCINT4/ADC4)PA4_33") (pintype "bidirectional"))
    )
    (net (code "57") (name "unconnected-(IC1-(PCINT5{slash}ADC5)PA5-Pad32)") (class "Default")
      (node (ref "IC1") (pin "32") (pinfunction "(PCINT5/ADC5)PA5_32") (pintype "bidirectional"))
    )
    (net (code "58") (name "unconnected-(IC1-(PCINT6{slash}ADC6)PA6-Pad31)") (class "Default")
      (node (ref "IC1") (pin "31") (pinfunction "(PCINT6/ADC6)PA6_31") (pintype "bidirectional"))
    )
    (net (code "59") (name "unconnected-(IC1-(PCINT7{slash}ADC7)PA7-Pad30)") (class "Default")
      (node (ref "IC1") (pin "30") (pinfunction "(PCINT7/ADC7)PA7_30") (pintype "bidirectional"))
    )
    (net (code "60") (name "unconnected-(IC1-(PCINT8{slash}XCK0{slash}T0)PB0-Pad40)") (class "Default")
      (node (ref "IC1") (pin "40") (pinfunction "(PCINT8/XCK0/T0)PB0_40") (pintype "bidirectional"))
    )
    (net (code "61") (name "unconnected-(IC1-(PCINT20{slash}TDO)PC4-Pad23)") (class "Default")
      (node (ref "IC1") (pin "23") (pinfunction "(PCINT20/TDO)PC4_23") (pintype "output"))
    )
    (net (code "62") (name "unconnected-(IC1-(PCINT21{slash}TDI)PC5-Pad24)") (class "Default")
      (node (ref "IC1") (pin "24") (pinfunction "(PCINT21/TDI)PC5_24") (pintype "output"))
    )
    (net (code "63") (name "unconnected-(IC1-(PCINT22{slash}TOSC1)PC6-Pad25)") (class "Default")
      (node (ref "IC1") (pin "25") (pinfunction "(PCINT22/TOSC1)PC6_25") (pintype "output"))
    )
    (net (code "64") (name "unconnected-(IC1-(PCINT23{slash}TOSC2)PC7-Pad26)") (class "Default")
      (node (ref "IC1") (pin "26") (pinfunction "(PCINT23/TOSC2)PC7_26") (pintype "output"))
    )
    (net (code "65") (name "unconnected-(MICRO_USB-ID-Pad4)") (class "Default")
      (node (ref "MICRO_USB") (pin "4") (pinfunction "ID_4") (pintype "passive"))
    )
    (net (code "66") (name "unconnected-(RTC1-32KHZ-Pad1)") (class "Default")
      (node (ref "RTC1") (pin "1") (pinfunction "32KHZ_1") (pintype "output"))
    )
    (net (code "67") (name "unconnected-(RTC1-RST-Pad4)") (class "Default")
      (node (ref "RTC1") (pin "4") (pinfunction "RST_4") (pintype "bidirectional"))
    )
    (net (code "68") (name "unconnected-(U$3-DAT1-Pad8)") (class "Default")
      (node (ref "U$3") (pin "8") (pinfunction "DAT1_8") (pintype "bidirectional"))
    )
    (net (code "69") (name "unconnected-(U$3-DAT2-Pad9)") (class "Default")
      (node (ref "U$3") (pin "9") (pinfunction "DAT2_9") (pintype "bidirectional"))
    )
    (net (code "70") (name "unconnected-(U$3-WRITE_PROTECT-PadWP)") (class "Default")
      (node (ref "U$3") (pin "WP") (pinfunction "WRITE_PROTECT_WP") (pintype "passive"))
    )
    (net (code "71") (name "unconnected-(U2-CBUS0-Pad15)") (class "Default")
      (node (ref "U2") (pin "15") (pinfunction "CBUS0_15") (pintype "bidirectional"))
    )
    (net (code "72") (name "unconnected-(U2-CBUS3-Pad16)") (class "Default")
      (node (ref "U2") (pin "16") (pinfunction "CBUS3_16") (pintype "bidirectional"))
    )
    (net (code "73") (name "unconnected-(U2-DCD#-Pad5)") (class "Default")
      (node (ref "U2") (pin "5") (pinfunction "DCD#_5") (pintype "bidirectional"))
    )
    (net (code "74") (name "unconnected-(U2-DSR#-Pad4)") (class "Default")
      (node (ref "U2") (pin "4") (pinfunction "DSR#_4") (pintype "bidirectional"))
    )
    (net (code "75") (name "unconnected-(U2-RI#-Pad2)") (class "Default")
      (node (ref "U2") (pin "2") (pinfunction "RI#_2") (pintype "bidirectional"))
    )
    (net (code "76") (name "unconnected-(U2-RTS#-Pad19)") (class "Default")
      (node (ref "U2") (pin "19") (pinfunction "RTS#_19") (pintype "bidirectional"))
    )
  )
)
